# solarpanel2.net
KiCad netlist of a schematic drawn in EAGLE
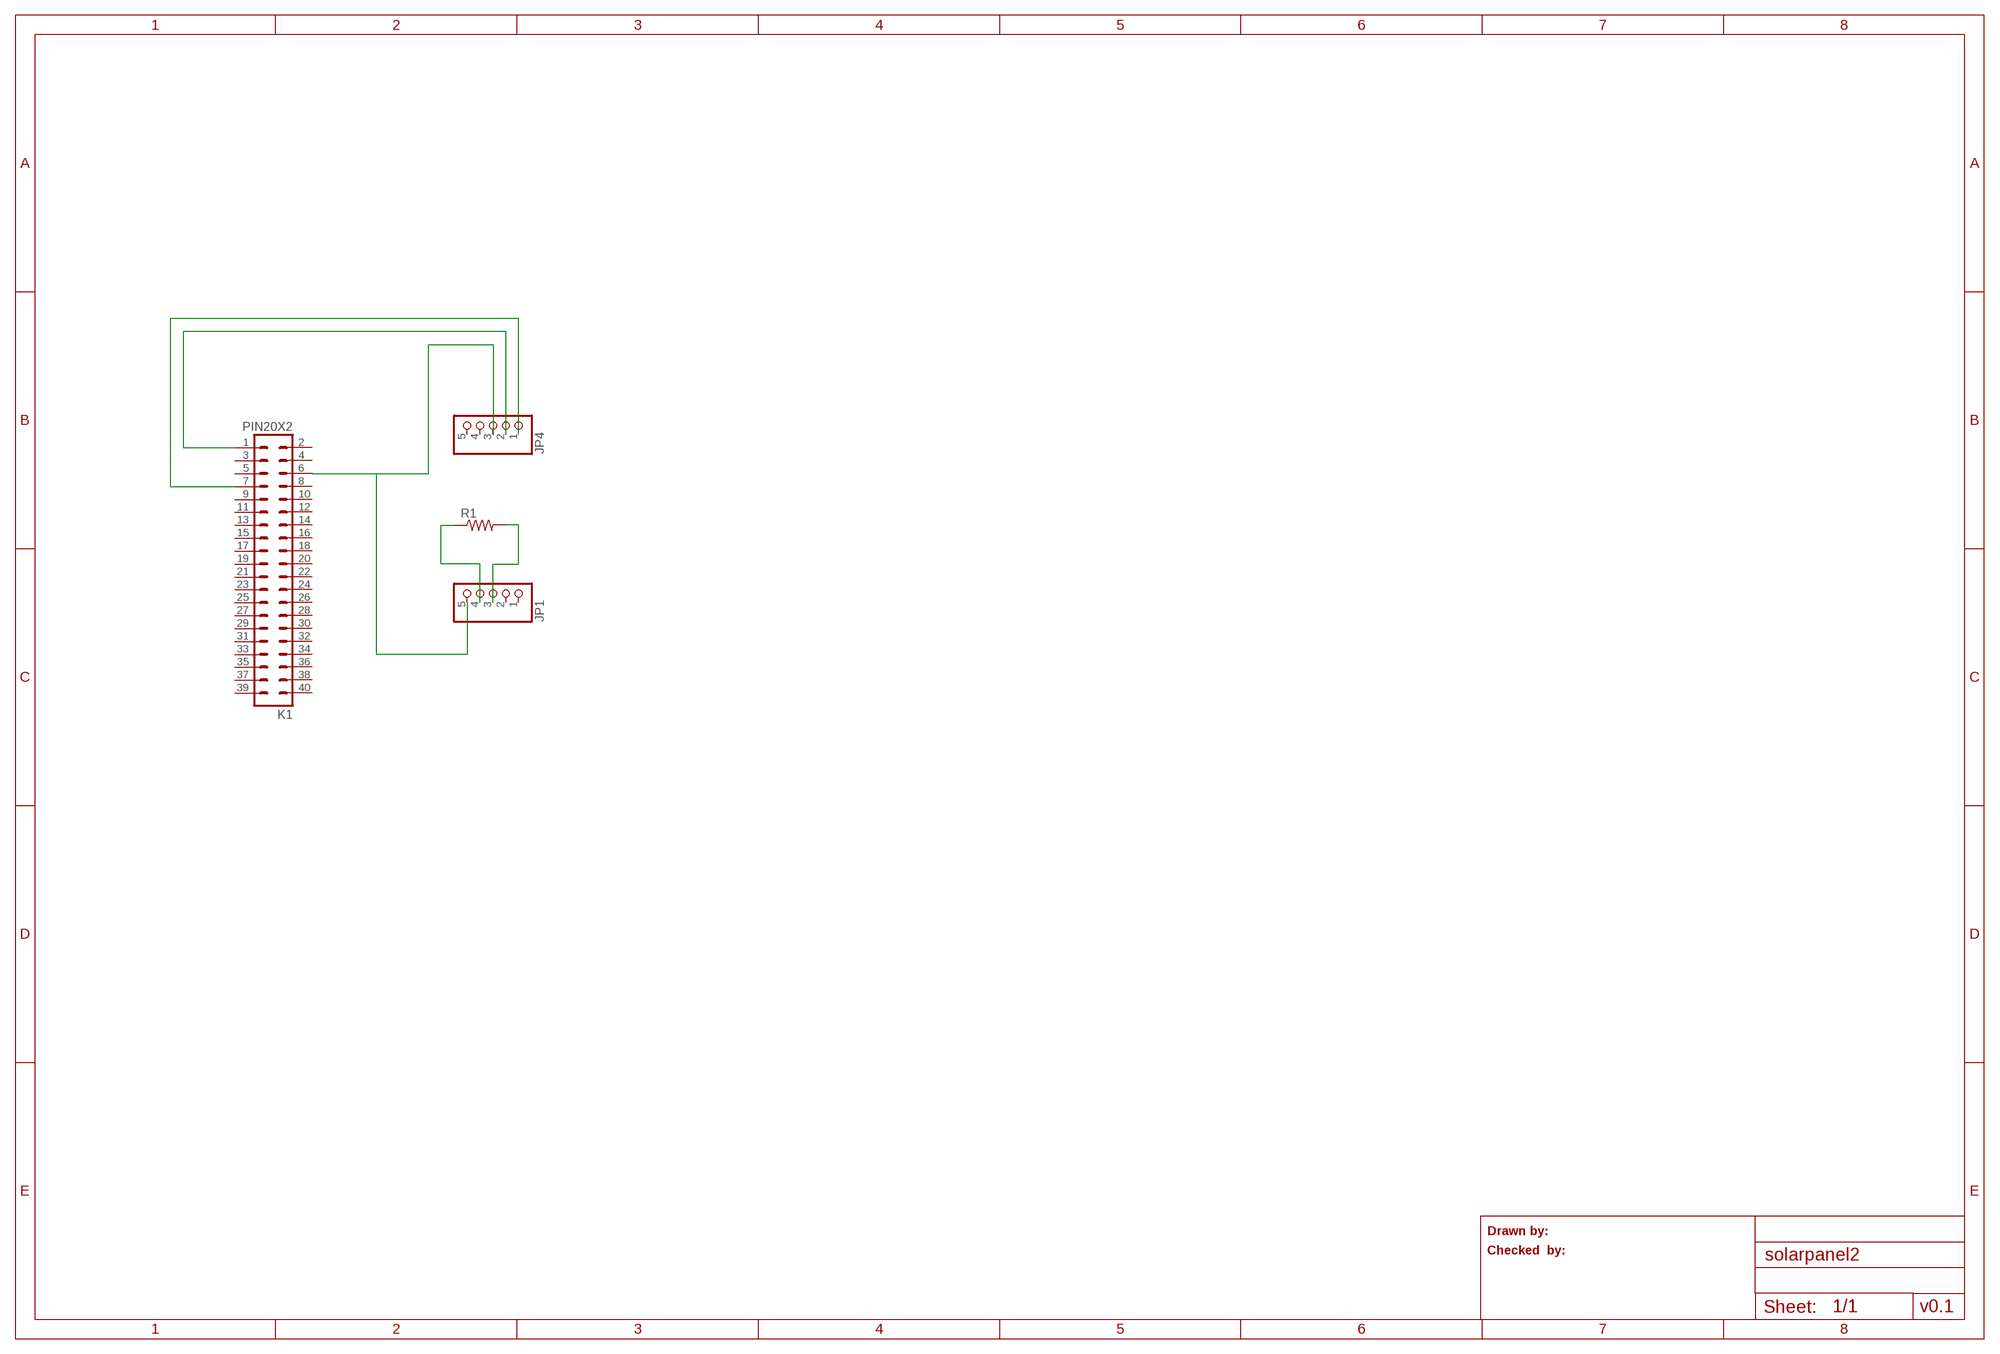
[diagram p0: schematic, sheet 1]

(export (version "E")
  (design (tool "Eeschema 10.0.6"))
  (components
    (comp (ref "JP1")
      (value "PINHD-1X5")
      (footprint "eagle-import:1X05")
      (libsource (lib "eagle-import") (part "PINHD-1X5"))
    )
    (comp (ref "JP4")
      (value "PINHD-1X5")
      (footprint "eagle-import:1X05")
      (libsource (lib "eagle-import") (part "PINHD-1X5"))
    )
    (comp (ref "K1")
      (value "PIN20X2")
      (footprint "eagle-import:PIN_20X2")
      (libsource (lib "eagle-import") (part "PIN20X2"))
    )
    (comp (ref "R1")
      (value "R-US_0207/10")
      (footprint "eagle-import:0207_10")
      (libsource (lib "eagle-import") (part "R-US_0207/10"))
    )
  )
  (nets
    (net (code "1") (name "Net-(JP1-Pad3)") (class "Default")
      (node (ref "JP1") (pin "3") (pinfunction "3_3") (pintype "passive"))
      (node (ref "R1") (pin "2") (pinfunction "2_2") (pintype "passive"))
    )
    (net (code "2") (name "Net-(JP1-Pad4)") (class "Default")
      (node (ref "JP1") (pin "4") (pinfunction "4_4") (pintype "passive"))
      (node (ref "R1") (pin "1") (pinfunction "1_1") (pintype "passive"))
    )
    (net (code "3") (name "Net-(JP1-Pad5)") (class "Default")
      (node (ref "JP1") (pin "5") (pinfunction "5_5") (pintype "passive"))
      (node (ref "JP4") (pin "3") (pinfunction "3_3") (pintype "passive"))
      (node (ref "K1") (pin "6") (pinfunction "6_6") (pintype "passive"))
    )
    (net (code "4") (name "Net-(JP4-Pad1)") (class "Default")
      (node (ref "JP4") (pin "1") (pinfunction "1_1") (pintype "passive"))
      (node (ref "K1") (pin "7") (pinfunction "7_7") (pintype "passive"))
    )
    (net (code "5") (name "Net-(JP4-Pad2)") (class "Default")
      (node (ref "JP4") (pin "2") (pinfunction "2_2") (pintype "passive"))
      (node (ref "K1") (pin "1") (pinfunction "1_1") (pintype "passive"))
    )
    (net (code "6") (name "unconnected-(JP1-Pad1)") (class "Default")
      (node (ref "JP1") (pin "1") (pinfunction "1_1") (pintype "passive"))
    )
    (net (code "7") (name "unconnected-(JP1-Pad2)") (class "Default")
      (node (ref "JP1") (pin "2") (pinfunction "2_2") (pintype "passive"))
    )
    (net (code "8") (name "unconnected-(JP4-Pad4)") (class "Default")
      (node (ref "JP4") (pin "4") (pinfunction "4_4") (pintype "passive"))
    )
    (net (code "9") (name "unconnected-(JP4-Pad5)") (class "Default")
      (node (ref "JP4") (pin "5") (pinfunction "5_5") (pintype "passive"))
    )
    (net (code "10") (name "unconnected-(K1-Pad2)") (class "Default")
      (node (ref "K1") (pin "2") (pinfunction "2_2") (pintype "passive"))
    )
    (net (code "11") (name "unconnected-(K1-Pad3)") (class "Default")
      (node (ref "K1") (pin "3") (pinfunction "3_3") (pintype "passive"))
    )
    (net (code "12") (name "unconnected-(K1-Pad4)") (class "Default")
      (node (ref "K1") (pin "4") (pinfunction "4_4") (pintype "passive"))
    )
    (net (code "13") (name "unconnected-(K1-Pad5)") (class "Default")
      (node (ref "K1") (pin "5") (pinfunction "5_5") (pintype "passive"))
    )
    (net (code "14") (name "unconnected-(K1-Pad8)") (class "Default")
      (node (ref "K1") (pin "8") (pinfunction "8_8") (pintype "passive"))
    )
    (net (code "15") (name "unconnected-(K1-Pad9)") (class "Default")
      (node (ref "K1") (pin "9") (pinfunction "9_9") (pintype "passive"))
    )
    (net (code "16") (name "unconnected-(K1-Pad10)") (class "Default")
      (node (ref "K1") (pin "10") (pinfunction "10_10") (pintype "passive"))
    )
    (net (code "17") (name "unconnected-(K1-Pad11)") (class "Default")
      (node (ref "K1") (pin "11") (pinfunction "11_11") (pintype "passive"))
    )
    (net (code "18") (name "unconnected-(K1-Pad12)") (class "Default")
      (node (ref "K1") (pin "12") (pinfunction "12_12") (pintype "passive"))
    )
    (net (code "19") (name "unconnected-(K1-Pad13)") (class "Default")
      (node (ref "K1") (pin "13") (pinfunction "13_13") (pintype "passive"))
    )
    (net (code "20") (name "unconnected-(K1-Pad14)") (class "Default")
      (node (ref "K1") (pin "14") (pinfunction "14_14") (pintype "passive"))
    )
    (net (code "21") (name "unconnected-(K1-Pad15)") (class "Default")
      (node (ref "K1") (pin "15") (pinfunction "15_15") (pintype "passive"))
    )
    (net (code "22") (name "unconnected-(K1-Pad16)") (class "Default")
      (node (ref "K1") (pin "16") (pinfunction "16_16") (pintype "passive"))
    )
    (net (code "23") (name "unconnected-(K1-Pad17)") (class "Default")
      (node (ref "K1") (pin "17") (pinfunction "17_17") (pintype "passive"))
    )
    (net (code "24") (name "unconnected-(K1-Pad18)") (class "Default")
      (node (ref "K1") (pin "18") (pinfunction "18_18") (pintype "passive"))
    )
    (net (code "25") (name "unconnected-(K1-Pad19)") (class "Default")
      (node (ref "K1") (pin "19") (pinfunction "19_19") (pintype "passive"))
    )
    (net (code "26") (name "unconnected-(K1-Pad20)") (class "Default")
      (node (ref "K1") (pin "20") (pinfunction "20_20") (pintype "passive"))
    )
    (net (code "27") (name "unconnected-(K1-Pad21)") (class "Default")
      (node (ref "K1") (pin "21") (pinfunction "21_21") (pintype "passive"))
    )
    (net (code "28") (name "unconnected-(K1-Pad22)") (class "Default")
      (node (ref "K1") (pin "22") (pinfunction "22_22") (pintype "passive"))
    )
    (net (code "29") (name "unconnected-(K1-Pad23)") (class "Default")
      (node (ref "K1") (pin "23") (pinfunction "23_23") (pintype "passive"))
    )
    (net (code "30") (name "unconnected-(K1-Pad24)") (class "Default")
      (node (ref "K1") (pin "24") (pinfunction "24_24") (pintype "passive"))
    )
    (net (code "31") (name "unconnected-(K1-Pad25)") (class "Default")
      (node (ref "K1") (pin "25") (pinfunction "25_25") (pintype "passive"))
    )
    (net (code "32") (name "unconnected-(K1-Pad26)") (class "Default")
      (node (ref "K1") (pin "26") (pinfunction "26_26") (pintype "passive"))
    )
    (net (code "33") (name "unconnected-(K1-Pad27)") (class "Default")
      (node (ref "K1") (pin "27") (pinfunction "27_27") (pintype "passive"))
    )
    (net (code "34") (name "unconnected-(K1-Pad28)") (class "Default")
      (node (ref "K1") (pin "28") (pinfunction "28_28") (pintype "passive"))
    )
    (net (code "35") (name "unconnected-(K1-Pad29)") (class "Default")
      (node (ref "K1") (pin "29") (pinfunction "29_29") (pintype "passive"))
    )
    (net (code "36") (name "unconnected-(K1-Pad30)") (class "Default")
      (node (ref "K1") (pin "30") (pinfunction "30_30") (pintype "passive"))
    )
    (net (code "37") (name "unconnected-(K1-Pad31)") (class "Default")
      (node (ref "K1") (pin "31") (pinfunction "31_31") (pintype "passive"))
    )
    (net (code "38") (name "unconnected-(K1-Pad32)") (class "Default")
      (node (ref "K1") (pin "32") (pinfunction "32_32") (pintype "passive"))
    )
    (net (code "39") (name "unconnected-(K1-Pad33)") (class "Default")
      (node (ref "K1") (pin "33") (pinfunction "33_33") (pintype "passive"))
    )
    (net (code "40") (name "unconnected-(K1-Pad34)") (class "Default")
      (node (ref "K1") (pin "34") (pinfunction "34_34") (pintype "passive"))
    )
    (net (code "41") (name "unconnected-(K1-Pad35)") (class "Default")
      (node (ref "K1") (pin "35") (pinfunction "35_35") (pintype "passive"))
    )
    (net (code "42") (name "unconnected-(K1-Pad36)") (class "Default")
      (node (ref "K1") (pin "36") (pinfunction "36_36") (pintype "passive"))
    )
    (net (code "43") (name "unconnected-(K1-Pad37)") (class "Default")
      (node (ref "K1") (pin "37") (pinfunction "37_37") (pintype "passive"))
    )
    (net (code "44") (name "unconnected-(K1-Pad38)") (class "Default")
      (node (ref "K1") (pin "38") (pinfunction "38_38") (pintype "passive"))
    )
    (net (code "45") (name "unconnected-(K1-Pad39)") (class "Default")
      (node (ref "K1") (pin "39") (pinfunction "39_39") (pintype "passive"))
    )
    (net (code "46") (name "unconnected-(K1-Pad40)") (class "Default")
      (node (ref "K1") (pin "40") (pinfunction "40_40") (pintype "passive"))
    )
  )
)
